# MCU_IMU.net
KiCad netlist of a schematic drawn in Altium Designer
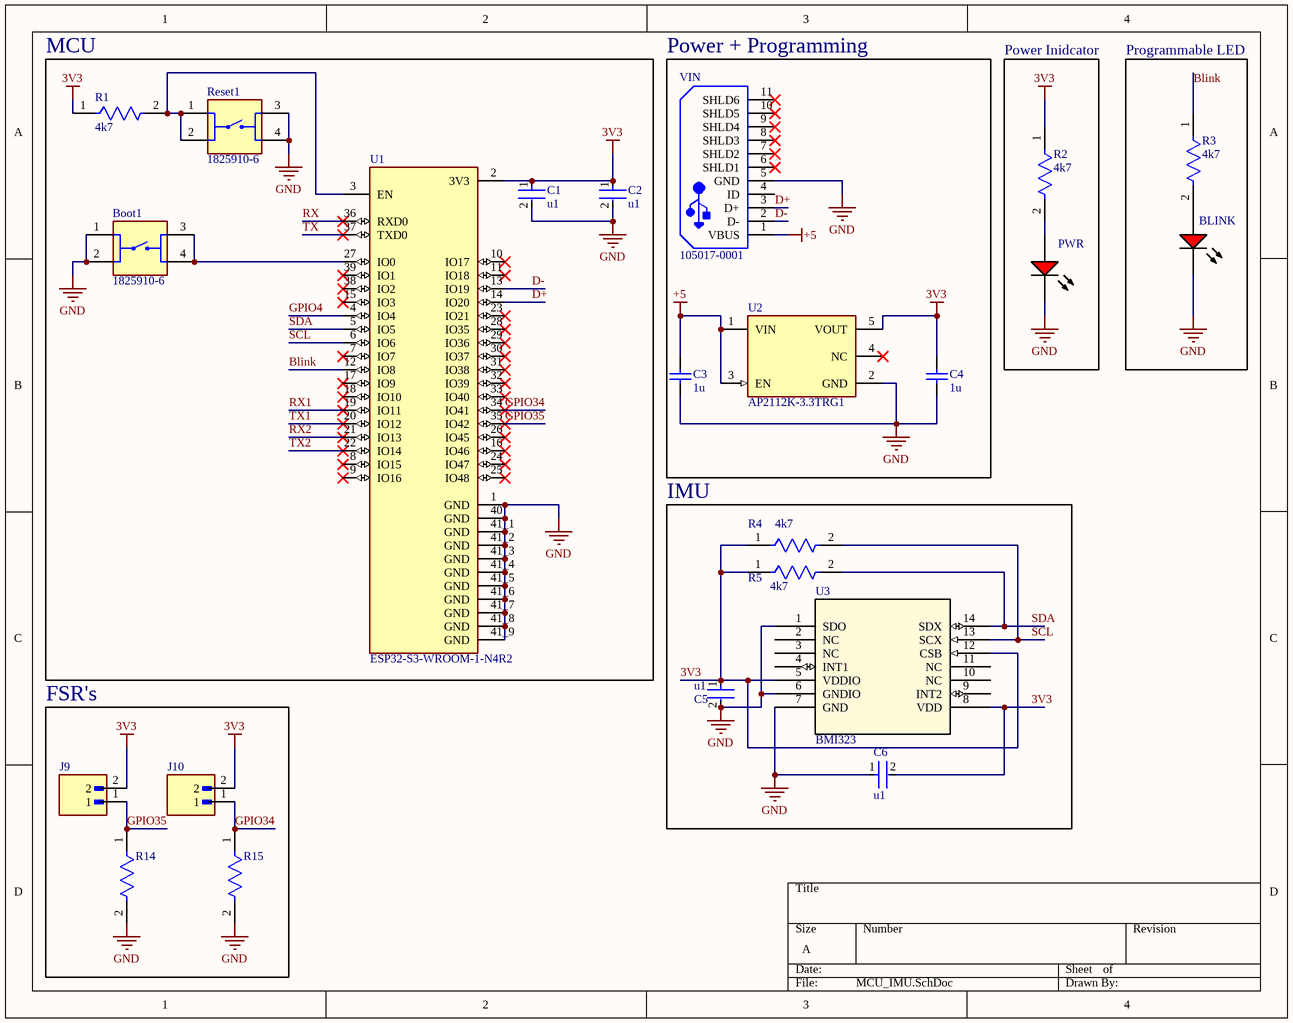
[diagram p0: MCU_IMU.SchDoc]

(export (version "E")
  (design (tool "Eeschema 10.0.6"))
  (components
    (comp (ref "BLINK")
      (value "SML-LX1206IC-TR")
      (footprint "LUMX-SML-LX1206IC_V")
      (description "LED Red, 65 mW, -40 to 85 degC, 2-Pin SMD, RoHS, Tape and Reel")
      (fields (field (name "MANUFACTURER") "Lumex"))
      (libsource (lib "Altium Content Vault") (part "LED-RED-AK-2"))
    )
    (comp (ref "Boot1")
      (value "1825910-6")
      (footprint "SW_1825910-6-4")
      (description "Switch Push Button OFF (ON) SPST Round Button 0.05A 24VDC Momentary Contact PC Pins Thru-Hole")
      (fields (field (name "MF") "TE Connectivity") (field (name "DIGI-KEY_PART_NUMBER") "450-1650-ND"))
      (libsource (lib "First") (part "1825910-6"))
    )
    (comp (ref "C1")
      (value "u1")
      (footprint "FP-CC0805-0_85-MFG")
      (description "CC0805KRX7R9BB104 CAP CER 0.1UF 50V X7R 0805")
      (fields (field (name "TOLERANCE") "0.1") (field (name "MANUFACTURER PART NUMBER") "CC0805KRX7R9BB104"))
      (libsource (lib "Altium Content Vault") (part "11868f565c42a9108669ba33697ecf6"))
    )
    (comp (ref "C2")
      (value "u1")
      (footprint "FP-CC0805-0_85-MFG")
      (description "CC0805KRX7R9BB104 CAP CER 0.1UF 50V X7R 0805")
      (fields (field (name "TOLERANCE") "0.1") (field (name "MANUFACTURER PART NUMBER") "CC0805KRX7R9BB104"))
      (libsource (lib "Altium Content Vault") (part "11868f565c42a9108669ba33697ecf6"))
    )
    (comp (ref "C3")
      (value "1u")
      (footprint "CAPC2013X140X50ML20T25")
      (fields (field (name "MANUFACTURER") "Kemet") (field (name "PART NUMBER") "C0805C105K5RACTU"))
      (libsource (lib "Altium Content Vault") (part "CAP"))
    )
    (comp (ref "C4")
      (value "1u")
      (footprint "CAPC2013X140X50ML20T25")
      (fields (field (name "MANUFACTURER") "Kemet") (field (name "PART NUMBER") "C0805C105K5RACTU"))
      (libsource (lib "Altium Content Vault") (part "CAP"))
    )
    (comp (ref "C5")
      (value "u1")
      (footprint "FP-CC0805-0_85-MFG")
      (description "CC0805KRX7R9BB104 CAP CER 0.1UF 50V X7R 0805")
      (fields (field (name "TOLERANCE") "0.1") (field (name "MANUFACTURER PART NUMBER") "CC0805KRX7R9BB104"))
      (libsource (lib "Altium Content Vault") (part "11868f565c42a9108669ba33697ecf6"))
    )
    (comp (ref "C6")
      (value "u1")
      (footprint "FP-CC0805-0_85-MFG")
      (description "CC0805KRX7R9BB104 CAP CER 0.1UF 50V X7R 0805")
      (fields (field (name "TOLERANCE") "0.1") (field (name "MANUFACTURER PART NUMBER") "CC0805KRX7R9BB104"))
      (libsource (lib "Altium Content Vault") (part "11868f565c42a9108669ba33697ecf6"))
    )
    (comp (ref "J9")
      (value "M20-9990246")
      (footprint "HARWIN_M20-9990246")
      (description "2.54mm (0.1) Pitch SIL Vertical Throughboard Pin Header, 6.1mm mating pin height, tin, 2 contacts")
      (fields (field (name "MF") "Harwin"))
      (libsource (lib "Bryan Heddle") (part "M20-9990246"))
    )
    (comp (ref "J10")
      (value "M20-9990246")
      (footprint "HARWIN_M20-9990246")
      (description "2.54mm (0.1) Pitch SIL Vertical Throughboard Pin Header, 6.1mm mating pin height, tin, 2 contacts")
      (fields (field (name "MF") "Harwin"))
      (libsource (lib "Bryan Heddle") (part "M20-9990246"))
    )
    (comp (ref "PWR")
      (value "SML-LX1206IC-TR")
      (footprint "LUMX-SML-LX1206IC_V")
      (description "LED Red, 65 mW, -40 to 85 degC, 2-Pin SMD, RoHS, Tape and Reel")
      (fields (field (name "MANUFACTURER") "Lumex"))
      (libsource (lib "Altium Content Vault") (part "LED-RED-AK-2"))
    )
    (comp (ref "R1")
      (value "4k7")
      (footprint "FP-CRCW0805-e3-IPC_B")
      (description "CRCW08054K70FKEARES Thick Film, 4.7kΩ, 1%, 0.125W, 100ppm/°C, 0805")
      (fields (field (name "TOLERANCE") "1%"))
      (libsource (lib "Altium Content Vault") (part "1029c3af85768c4190bb7ad29bc67b5"))
    )
    (comp (ref "R2")
      (value "4k7")
      (footprint "FP-CRCW0805-e3-IPC_B")
      (description "CRCW08054K70FKEARES Thick Film, 4.7kΩ, 1%, 0.125W, 100ppm/°C, 0805")
      (fields (field (name "TOLERANCE") "1%"))
      (libsource (lib "Altium Content Vault") (part "1029c3af85768c4190bb7ad29bc67b5"))
    )
    (comp (ref "R3")
      (value "4k7")
      (footprint "FP-CRCW0805-e3-IPC_B")
      (description "CRCW08054K70FKEARES Thick Film, 4.7kΩ, 1%, 0.125W, 100ppm/°C, 0805")
      (fields (field (name "TOLERANCE") "1%"))
      (libsource (lib "Altium Content Vault") (part "1029c3af85768c4190bb7ad29bc67b5"))
    )
    (comp (ref "R4")
      (value "4k7")
      (footprint "FP-CRCW0805-e3-IPC_B")
      (description "CRCW08054K70FKEARES Thick Film, 4.7kΩ, 1%, 0.125W, 100ppm/°C, 0805")
      (fields (field (name "TOLERANCE") "1%"))
      (libsource (lib "Altium Content Vault") (part "1029c3af85768c4190bb7ad29bc67b5"))
    )
    (comp (ref "R5")
      (value "4k7")
      (footprint "FP-CRCW0805-e3-IPC_B")
      (description "CRCW08054K70FKEARES Thick Film, 4.7kΩ, 1%, 0.125W, 100ppm/°C, 0805")
      (fields (field (name "TOLERANCE") "1%"))
      (libsource (lib "Altium Content Vault") (part "1029c3af85768c4190bb7ad29bc67b5"))
    )
    (comp (ref "R14")
      (value "RMCF1206FG10K0")
      (footprint "FP-RMCF1206-MFG")
      (description "10kΩ ±1% 0.25W 1206 Thick Film Chip Resistor AEC-Q200 compliant")
      (fields (field (name "TOLERANCE") "1%"))
      (libsource (lib "Altium Content Vault") (part "1029c3af85768c4190bb7ad29bc67b5"))
    )
    (comp (ref "R15")
      (value "RMCF1206FG10K0")
      (footprint "FP-RMCF1206-MFG")
      (description "10kΩ ±1% 0.25W 1206 Thick Film Chip Resistor AEC-Q200 compliant")
      (fields (field (name "TOLERANCE") "1%"))
      (libsource (lib "Altium Content Vault") (part "1029c3af85768c4190bb7ad29bc67b5"))
    )
    (comp (ref "Reset1")
      (value "1825910-6")
      (footprint "SW_1825910-6-4")
      (description "Switch Push Button OFF (ON) SPST Round Button 0.05A 24VDC Momentary Contact PC Pins Thru-Hole")
      (fields (field (name "MF") "TE Connectivity") (field (name "DIGI-KEY_PART_NUMBER") "450-1650-ND"))
      (libsource (lib "First") (part "1825910-6"))
    )
    (comp (ref "U1")
      (value "ESP32-S3-WROOM-1-N4R2")
      (footprint "XCVR_ESP32-S3-WROOM-1-N4R2")
      (description "Bluetooth, WiFi 802.11b/g/n, Bluetooth v5.0 Transceiver Module 2.4GHz PCB Trace Surface Mount")
      (fields (field (name "MF") "Espressif Systems"))
      (libsource (lib "ESP32-S3-WROOM-1-N4R2") (part "ESP32-S3-WROOM-1-N4R2"))
    )
    (comp (ref "U2")
      (value "AP2112K-3.3TRG1")
      (footprint "FP-SOT25-IPC_A")
      (description "IC REG LINEAR 3.3V 600MA SOT25")
      (libsource (lib "Altium Content Vault") (part "c8ab751aee5229183125ab046a11caa"))
    )
    (comp (ref "U3")
      (value "BMI323")
      (footprint "BMI323_BOS")
      (description "No Description Available")
      (fields (field (name "COPYRIGHT") "Copyright (C) 2025 Ultra Librarian. All rights reserved."))
      (libsource (lib "AI_Project_Library") (part "BMI323"))
    )
    (comp (ref "VIN")
      (value "105017-0001")
      (footprint "USB-MICRO-B_V")
      (fields (field (name "MANUFACTURER") "Molex"))
      (libsource (lib "Altium Content Vault") (part "USB-5-6SHLD"))
    )
  )
  (nets
    (net (code "1") (name "+5") (class "Default")
      (node (ref "C3") (pin "2") (pinfunction "2_2") (pintype "passive"))
      (node (ref "U2") (pin "1") (pinfunction "VIN_1") (pintype "power_in"))
      (node (ref "U2") (pin "3") (pinfunction "EN_3") (pintype "input"))
      (node (ref "VIN") (pin "1") (pinfunction "VBUS_1") (pintype "passive"))
    )
    (net (code "2") (name "/Blink") (class "Default")
      (node (ref "R3") (pin "1") (pinfunction "1_1") (pintype "passive"))
      (node (ref "U1") (pin "12") (pinfunction "IO8_12") (pintype "bidirectional"))
    )
    (net (code "3") (name "/D+") (class "Default")
      (node (ref "U1") (pin "14") (pinfunction "IO20_14") (pintype "bidirectional"))
      (node (ref "VIN") (pin "3") (pinfunction "D+_3") (pintype "passive"))
    )
    (net (code "4") (name "/D-") (class "Default")
      (node (ref "U1") (pin "13") (pinfunction "IO19_13") (pintype "bidirectional"))
      (node (ref "VIN") (pin "2") (pinfunction "D-_2") (pintype "passive"))
    )
    (net (code "5") (name "/GPIO4") (class "Default")
      (node (ref "U1") (pin "4") (pinfunction "IO4_4") (pintype "bidirectional"))
    )
    (net (code "6") (name "/GPIO34") (class "Default")
      (node (ref "J10") (pin "1") (pinfunction "1_1") (pintype "passive"))
      (node (ref "R15") (pin "1") (pinfunction "1_1") (pintype "passive"))
      (node (ref "U1") (pin "34") (pinfunction "IO41_34") (pintype "bidirectional"))
    )
    (net (code "7") (name "/GPIO35") (class "Default")
      (node (ref "J9") (pin "1") (pinfunction "1_1") (pintype "passive"))
      (node (ref "R14") (pin "1") (pinfunction "1_1") (pintype "passive"))
      (node (ref "U1") (pin "35") (pinfunction "IO42_35") (pintype "bidirectional"))
    )
    (net (code "8") (name "/RX") (class "Default")
      (node (ref "U1") (pin "36") (pinfunction "RXD0_36") (pintype "bidirectional+no_connect"))
    )
    (net (code "9") (name "/RX1") (class "Default")
      (node (ref "U1") (pin "19") (pinfunction "IO11_19") (pintype "bidirectional+no_connect"))
    )
    (net (code "10") (name "/RX2") (class "Default")
      (node (ref "U1") (pin "21") (pinfunction "IO13_21") (pintype "bidirectional+no_connect"))
    )
    (net (code "11") (name "/SCL") (class "Default")
      (node (ref "R4") (pin "2") (pinfunction "2_2") (pintype "passive"))
      (node (ref "U1") (pin "6") (pinfunction "IO6_6") (pintype "bidirectional"))
      (node (ref "U3") (pin "13") (pinfunction "SCX_13") (pintype "input"))
    )
    (net (code "12") (name "/SDA") (class "Default")
      (node (ref "R5") (pin "2") (pinfunction "2_2") (pintype "passive"))
      (node (ref "U1") (pin "5") (pinfunction "IO5_5") (pintype "bidirectional"))
      (node (ref "U3") (pin "14") (pinfunction "SDX_14") (pintype "bidirectional"))
    )
    (net (code "13") (name "/TX") (class "Default")
      (node (ref "U1") (pin "37") (pinfunction "TXD0_37") (pintype "bidirectional+no_connect"))
    )
    (net (code "14") (name "/TX1") (class "Default")
      (node (ref "U1") (pin "20") (pinfunction "IO12_20") (pintype "bidirectional+no_connect"))
    )
    (net (code "15") (name "/TX2") (class "Default")
      (node (ref "U1") (pin "22") (pinfunction "IO14_22") (pintype "bidirectional+no_connect"))
    )
    (net (code "16") (name "3V3") (class "Default")
      (node (ref "C1") (pin "1") (pinfunction "1_1") (pintype "passive"))
      (node (ref "C2") (pin "1") (pinfunction "1_1") (pintype "passive"))
      (node (ref "C4") (pin "2") (pinfunction "2_2") (pintype "passive"))
      (node (ref "C5") (pin "1") (pinfunction "1_1") (pintype "passive"))
      (node (ref "C6") (pin "2") (pinfunction "2_2") (pintype "passive"))
      (node (ref "J10") (pin "2") (pinfunction "2_2") (pintype "passive"))
      (node (ref "J9") (pin "2") (pinfunction "2_2") (pintype "passive"))
      (node (ref "R1") (pin "1") (pinfunction "1_1") (pintype "passive"))
      (node (ref "R2") (pin "1") (pinfunction "1_1") (pintype "passive"))
      (node (ref "R4") (pin "1") (pinfunction "1_1") (pintype "passive"))
      (node (ref "R5") (pin "1") (pinfunction "1_1") (pintype "passive"))
      (node (ref "U1") (pin "2") (pinfunction "3V3_2") (pintype "power_in"))
      (node (ref "U2") (pin "5") (pinfunction "VOUT_5") (pintype "power_in"))
      (node (ref "U3") (pin "12") (pinfunction "CSB_12") (pintype "input"))
      (node (ref "U3") (pin "5") (pinfunction "VDDIO_5") (pintype "power_in"))
      (node (ref "U3") (pin "8") (pinfunction "VDD_8") (pintype "power_in"))
    )
    (net (code "17") (name "GND") (class "Default")
      (node (ref "BLINK") (pin "2") (pinfunction "K_2") (pintype "passive"))
      (node (ref "Boot1") (pin "1") (pinfunction "1_1") (pintype "passive"))
      (node (ref "Boot1") (pin "2") (pinfunction "2_2") (pintype "passive"))
      (node (ref "C1") (pin "2") (pinfunction "2_2") (pintype "passive"))
      (node (ref "C2") (pin "2") (pinfunction "2_2") (pintype "passive"))
      (node (ref "C3") (pin "1") (pinfunction "1_1") (pintype "passive"))
      (node (ref "C4") (pin "1") (pinfunction "1_1") (pintype "passive"))
      (node (ref "C5") (pin "2") (pinfunction "2_2") (pintype "passive"))
      (node (ref "C6") (pin "1") (pinfunction "1_1") (pintype "passive"))
      (node (ref "PWR") (pin "2") (pinfunction "K_2") (pintype "passive"))
      (node (ref "R14") (pin "2") (pinfunction "2_2") (pintype "passive"))
      (node (ref "R15") (pin "2") (pinfunction "2_2") (pintype "passive"))
      (node (ref "Reset1") (pin "3") (pinfunction "3_3") (pintype "passive"))
      (node (ref "Reset1") (pin "4") (pinfunction "4_4") (pintype "passive"))
      (node (ref "U1") (pin "1") (pinfunction "GND_1") (pintype "power_in"))
      (node (ref "U1") (pin "40") (pinfunction "GND_40") (pintype "power_in"))
      (node (ref "U1") (pin "41_1") (pinfunction "GND_41_1") (pintype "power_in"))
      (node (ref "U1") (pin "41_2") (pinfunction "GND_41_2") (pintype "power_in"))
      (node (ref "U1") (pin "41_3") (pinfunction "GND_41_3") (pintype "power_in"))
      (node (ref "U1") (pin "41_4") (pinfunction "GND_41_4") (pintype "power_in"))
      (node (ref "U1") (pin "41_5") (pinfunction "GND_41_5") (pintype "power_in"))
      (node (ref "U1") (pin "41_6") (pinfunction "GND_41_6") (pintype "power_in"))
      (node (ref "U1") (pin "41_7") (pinfunction "GND_41_7") (pintype "power_in"))
      (node (ref "U1") (pin "41_8") (pinfunction "GND_41_8") (pintype "power_in"))
      (node (ref "U1") (pin "41_9") (pinfunction "GND_41_9") (pintype "power_in"))
      (node (ref "U2") (pin "2") (pinfunction "GND_2") (pintype "power_in"))
      (node (ref "U3") (pin "1") (pinfunction "SDO_1") (pintype "passive"))
      (node (ref "U3") (pin "6") (pinfunction "GNDIO_6") (pintype "power_in"))
      (node (ref "U3") (pin "7") (pinfunction "GND_7") (pintype "power_in"))
      (node (ref "VIN") (pin "5") (pinfunction "GND_5") (pintype "passive"))
    )
    (net (code "18") (name "Net-(BLINK-A)") (class "Default")
      (node (ref "BLINK") (pin "1") (pinfunction "A_1") (pintype "passive"))
      (node (ref "R3") (pin "2") (pinfunction "2_2") (pintype "passive"))
    )
    (net (code "19") (name "Net-(PWR-A)") (class "Default")
      (node (ref "PWR") (pin "1") (pinfunction "A_1") (pintype "passive"))
      (node (ref "R2") (pin "2") (pinfunction "2_2") (pintype "passive"))
    )
    (net (code "20") (name "Net-(U1-EN)") (class "Default")
      (node (ref "R1") (pin "2") (pinfunction "2_2") (pintype "passive"))
      (node (ref "Reset1") (pin "1") (pinfunction "1_1") (pintype "passive"))
      (node (ref "Reset1") (pin "2") (pinfunction "2_2") (pintype "passive"))
      (node (ref "U1") (pin "3") (pinfunction "EN_3") (pintype "power_in"))
    )
    (net (code "21") (name "Net-(U1-IO0)") (class "Default")
      (node (ref "Boot1") (pin "3") (pinfunction "3_3") (pintype "passive"))
      (node (ref "Boot1") (pin "4") (pinfunction "4_4") (pintype "passive"))
      (node (ref "U1") (pin "27") (pinfunction "IO0_27") (pintype "bidirectional"))
    )
    (net (code "22") (name "unconnected-(U1-IO1-Pad39)") (class "Default")
      (node (ref "U1") (pin "39") (pinfunction "IO1_39") (pintype "bidirectional+no_connect"))
    )
    (net (code "23") (name "unconnected-(U1-IO2-Pad38)") (class "Default")
      (node (ref "U1") (pin "38") (pinfunction "IO2_38") (pintype "bidirectional+no_connect"))
    )
    (net (code "24") (name "unconnected-(U1-IO3-Pad15)") (class "Default")
      (node (ref "U1") (pin "15") (pinfunction "IO3_15") (pintype "bidirectional+no_connect"))
    )
    (net (code "25") (name "unconnected-(U1-IO7-Pad7)") (class "Default")
      (node (ref "U1") (pin "7") (pinfunction "IO7_7") (pintype "bidirectional+no_connect"))
    )
    (net (code "26") (name "unconnected-(U1-IO9-Pad17)") (class "Default")
      (node (ref "U1") (pin "17") (pinfunction "IO9_17") (pintype "bidirectional+no_connect"))
    )
    (net (code "27") (name "unconnected-(U1-IO10-Pad18)") (class "Default")
      (node (ref "U1") (pin "18") (pinfunction "IO10_18") (pintype "bidirectional+no_connect"))
    )
    (net (code "28") (name "unconnected-(U1-IO15-Pad8)") (class "Default")
      (node (ref "U1") (pin "8") (pinfunction "IO15_8") (pintype "bidirectional+no_connect"))
    )
    (net (code "29") (name "unconnected-(U1-IO16-Pad9)") (class "Default")
      (node (ref "U1") (pin "9") (pinfunction "IO16_9") (pintype "bidirectional+no_connect"))
    )
    (net (code "30") (name "unconnected-(U1-IO17-Pad10)") (class "Default")
      (node (ref "U1") (pin "10") (pinfunction "IO17_10") (pintype "bidirectional+no_connect"))
    )
    (net (code "31") (name "unconnected-(U1-IO18-Pad11)") (class "Default")
      (node (ref "U1") (pin "11") (pinfunction "IO18_11") (pintype "bidirectional+no_connect"))
    )
    (net (code "32") (name "unconnected-(U1-IO21-Pad23)") (class "Default")
      (node (ref "U1") (pin "23") (pinfunction "IO21_23") (pintype "bidirectional+no_connect"))
    )
    (net (code "33") (name "unconnected-(U1-IO35-Pad28)") (class "Default")
      (node (ref "U1") (pin "28") (pinfunction "IO35_28") (pintype "bidirectional+no_connect"))
    )
    (net (code "34") (name "unconnected-(U1-IO36-Pad29)") (class "Default")
      (node (ref "U1") (pin "29") (pinfunction "IO36_29") (pintype "bidirectional+no_connect"))
    )
    (net (code "35") (name "unconnected-(U1-IO37-Pad30)") (class "Default")
      (node (ref "U1") (pin "30") (pinfunction "IO37_30") (pintype "bidirectional+no_connect"))
    )
    (net (code "36") (name "unconnected-(U1-IO38-Pad31)") (class "Default")
      (node (ref "U1") (pin "31") (pinfunction "IO38_31") (pintype "bidirectional+no_connect"))
    )
    (net (code "37") (name "unconnected-(U1-IO39-Pad32)") (class "Default")
      (node (ref "U1") (pin "32") (pinfunction "IO39_32") (pintype "bidirectional+no_connect"))
    )
    (net (code "38") (name "unconnected-(U1-IO40-Pad33)") (class "Default")
      (node (ref "U1") (pin "33") (pinfunction "IO40_33") (pintype "bidirectional+no_connect"))
    )
    (net (code "39") (name "unconnected-(U1-IO45-Pad26)") (class "Default")
      (node (ref "U1") (pin "26") (pinfunction "IO45_26") (pintype "bidirectional+no_connect"))
    )
    (net (code "40") (name "unconnected-(U1-IO46-Pad16)") (class "Default")
      (node (ref "U1") (pin "16") (pinfunction "IO46_16") (pintype "bidirectional+no_connect"))
    )
    (net (code "41") (name "unconnected-(U1-IO47-Pad24)") (class "Default")
      (node (ref "U1") (pin "24") (pinfunction "IO47_24") (pintype "bidirectional+no_connect"))
    )
    (net (code "42") (name "unconnected-(U1-IO48-Pad25)") (class "Default")
      (node (ref "U1") (pin "25") (pinfunction "IO48_25") (pintype "bidirectional+no_connect"))
    )
    (net (code "43") (name "unconnected-(U2-NC-Pad4)") (class "Default")
      (node (ref "U2") (pin "4") (pinfunction "NC_4") (pintype "passive+no_connect"))
    )
    (net (code "44") (name "unconnected-(U3-INT1-Pad4)") (class "Default")
      (node (ref "U3") (pin "4") (pinfunction "INT1_4") (pintype "bidirectional"))
    )
    (net (code "45") (name "unconnected-(U3-INT2-Pad9)") (class "Default")
      (node (ref "U3") (pin "9") (pinfunction "INT2_9") (pintype "bidirectional"))
    )
    (net (code "46") (name "unconnected-(U3-NC-Pad2)") (class "Default")
      (node (ref "U3") (pin "2") (pinfunction "NC_2") (pintype "passive"))
    )
    (net (code "47") (name "unconnected-(U3-NC-Pad3)") (class "Default")
      (node (ref "U3") (pin "3") (pinfunction "NC_3") (pintype "passive"))
    )
    (net (code "48") (name "unconnected-(U3-NC-Pad10)") (class "Default")
      (node (ref "U3") (pin "10") (pinfunction "NC_10") (pintype "passive"))
    )
    (net (code "49") (name "unconnected-(U3-NC-Pad11)") (class "Default")
      (node (ref "U3") (pin "11") (pinfunction "NC_11") (pintype "passive"))
    )
    (net (code "50") (name "unconnected-(VIN-ID-Pad4)") (class "Default")
      (node (ref "VIN") (pin "4") (pinfunction "ID_4") (pintype "passive"))
    )
    (net (code "51") (name "unconnected-(VIN-SHLD1-Pad6)") (class "Default")
      (node (ref "VIN") (pin "6") (pinfunction "SHLD1_6") (pintype "passive+no_connect"))
    )
    (net (code "52") (name "unconnected-(VIN-SHLD2-Pad7)") (class "Default")
      (node (ref "VIN") (pin "7") (pinfunction "SHLD2_7") (pintype "passive+no_connect"))
    )
    (net (code "53") (name "unconnected-(VIN-SHLD3-Pad8)") (class "Default")
      (node (ref "VIN") (pin "8") (pinfunction "SHLD3_8") (pintype "passive+no_connect"))
    )
    (net (code "54") (name "unconnected-(VIN-SHLD4-Pad9)") (class "Default")
      (node (ref "VIN") (pin "9") (pinfunction "SHLD4_9") (pintype "passive+no_connect"))
    )
    (net (code "55") (name "unconnected-(VIN-SHLD5-Pad10)") (class "Default")
      (node (ref "VIN") (pin "10") (pinfunction "SHLD5_10") (pintype "passive+no_connect"))
    )
    (net (code "56") (name "unconnected-(VIN-SHLD6-Pad11)") (class "Default")
      (node (ref "VIN") (pin "11") (pinfunction "SHLD6_11") (pintype "passive+no_connect"))
    )
  )
)
